# bq25798.net
KiCad netlist of a schematic drawn in Altium Designer
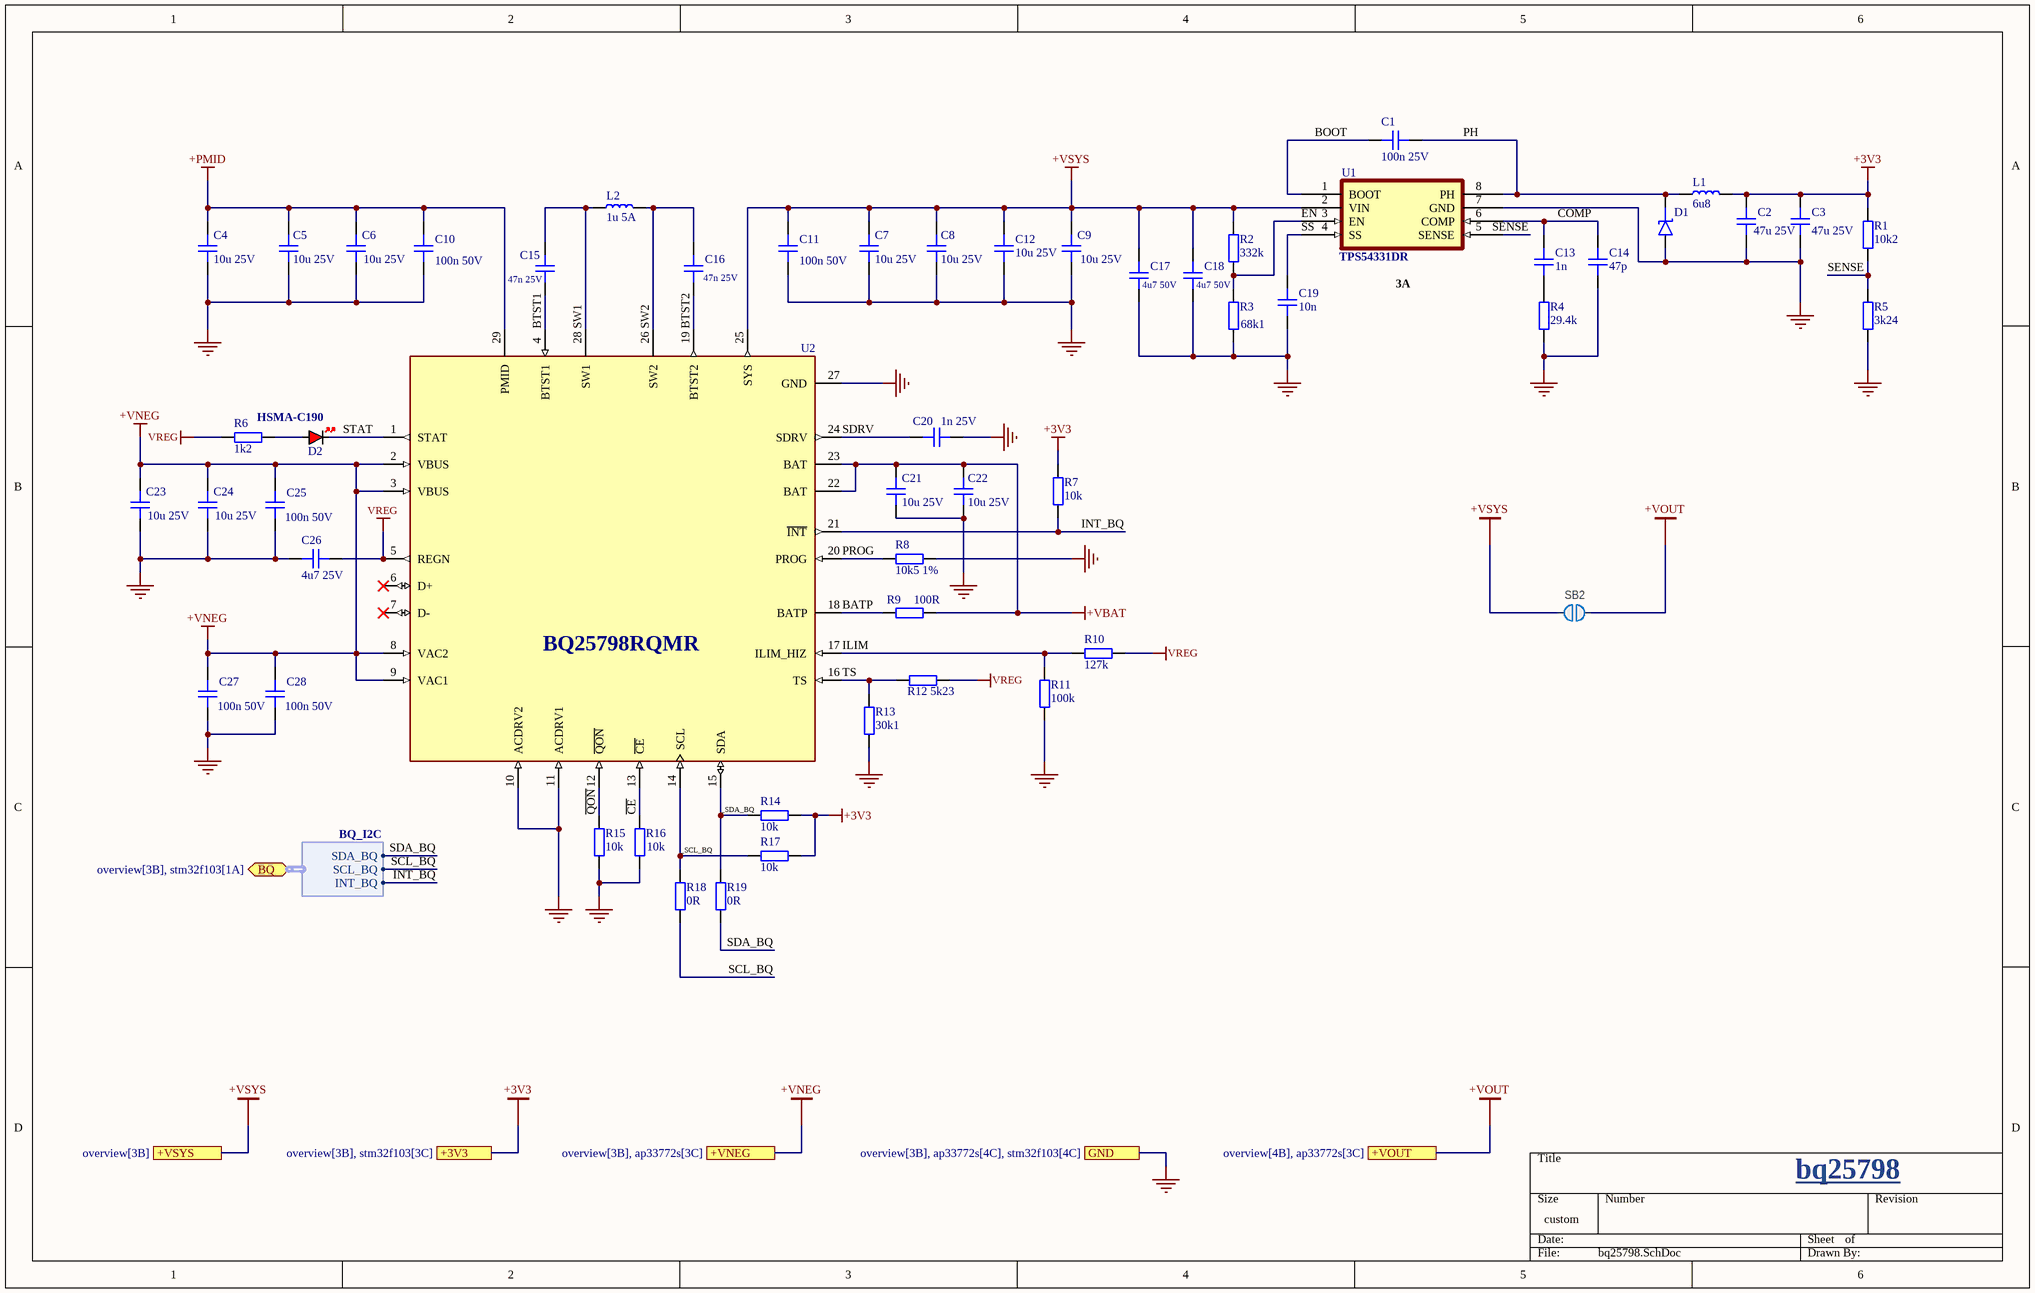
[diagram p0: bq25798.SchDoc]

(export (version "E")
  (design (tool "Eeschema 10.0.6"))
  (components
    (comp (ref "C1")
      (value "100n 25V")
      (footprint "CAP_0805")
      (description "Capacitor SMD 0805")
      (libsource (lib "Schematic-Lib-PhilsLab") (part "CAP_0805"))
    )
    (comp (ref "C2")
      (value "47u 25V")
      (footprint "CAP_1206")
      (description "Capacitor SMD 1206")
      (libsource (lib "Schematic-Lib-PhilsLab") (part "CAP_1206"))
    )
    (comp (ref "C3")
      (value "47u 25V")
      (footprint "CAP_1206")
      (description "Capacitor SMD 1206")
      (libsource (lib "Schematic-Lib-PhilsLab") (part "CAP_1206"))
    )
    (comp (ref "C4")
      (value "10u 25V")
      (footprint "CAP_0603")
      (description "Capacitor SMD 0603")
      (libsource (lib "Sch_Lib") (part "CAP_0603"))
    )
    (comp (ref "C5")
      (value "10u 25V")
      (footprint "CAP_0603")
      (description "Capacitor SMD 0603")
      (libsource (lib "Sch_Lib") (part "CAP_0603"))
    )
    (comp (ref "C6")
      (value "10u 25V")
      (footprint "CAP_0603")
      (description "Capacitor SMD 0603")
      (libsource (lib "Sch_Lib") (part "CAP_0603"))
    )
    (comp (ref "C7")
      (value "10u 25V")
      (footprint "CAP_0603")
      (description "Capacitor SMD 0603")
      (libsource (lib "Sch_Lib") (part "CAP_0603"))
    )
    (comp (ref "C8")
      (value "10u 25V")
      (footprint "CAP_0603")
      (description "Capacitor SMD 0603")
      (libsource (lib "Sch_Lib") (part "CAP_0603"))
    )
    (comp (ref "C9")
      (value "10u 25V")
      (footprint "CAP_0603")
      (description "Capacitor SMD 0603")
      (libsource (lib "Sch_Lib") (part "CAP_0603"))
    )
    (comp (ref "C10")
      (value "100n 50V")
      (footprint "CAP_0402")
      (description "Capacitor SMD 0402")
      (libsource (lib "Sch_Lib") (part "CAP_0402"))
    )
    (comp (ref "C11")
      (value "100n 50V")
      (footprint "CAP_0402")
      (description "Capacitor SMD 0402")
      (libsource (lib "Sch_Lib") (part "CAP_0402"))
    )
    (comp (ref "C12")
      (value "10u 25V")
      (footprint "CAP_0603")
      (description "Capacitor SMD 0603")
      (libsource (lib "Sch_Lib") (part "CAP_0603"))
    )
    (comp (ref "C13")
      (value "1n")
      (footprint "CAP_0603")
      (description "Capacitor SMD 0603")
      (libsource (lib "Schematic-Lib-PhilsLab") (part "CAP_0603"))
    )
    (comp (ref "C14")
      (value "47p")
      (footprint "CAP_0402")
      (description "Capacitor SMD 0402")
      (libsource (lib "Schematic-Lib-PhilsLab") (part "CAP_0402"))
    )
    (comp (ref "C15")
      (value "47n 25V")
      (footprint "CAP_0603")
      (description "Capacitor SMD 0603")
      (libsource (lib "Sch_Lib") (part "CAP_0603"))
    )
    (comp (ref "C16")
      (value "47n 25V")
      (footprint "CAP_0603")
      (description "Capacitor SMD 0603")
      (libsource (lib "Sch_Lib") (part "CAP_0603"))
    )
    (comp (ref "C17")
      (value "4u7 50V")
      (footprint "CAP_1206")
      (description "Capacitor SMD 1206")
      (libsource (lib "Schematic-Lib-PhilsLab") (part "CAP_1206"))
    )
    (comp (ref "C18")
      (value "4u7 50V")
      (footprint "CAP_1206")
      (description "Capacitor SMD 1206")
      (libsource (lib "Schematic-Lib-PhilsLab") (part "CAP_1206"))
    )
    (comp (ref "C19")
      (value "10n")
      (footprint "CAP_0603")
      (description "Capacitor SMD 0603")
      (libsource (lib "Schematic-Lib-PhilsLab") (part "CAP_0603"))
    )
    (comp (ref "C20")
      (value "1n 25V")
      (footprint "CAP_0603")
      (description "Capacitor SMD 0603")
      (libsource (lib "Sch_Lib") (part "CAP_0603"))
    )
    (comp (ref "C21")
      (value "10u 25V")
      (footprint "CAP_0603")
      (description "Capacitor SMD 0603")
      (libsource (lib "Sch_Lib") (part "CAP_0603"))
    )
    (comp (ref "C22")
      (value "10u 25V")
      (footprint "CAP_0603")
      (description "Capacitor SMD 0603")
      (libsource (lib "Sch_Lib") (part "CAP_0603"))
    )
    (comp (ref "C23")
      (value "10u 25V")
      (footprint "CAP_0603")
      (description "Capacitor SMD 0603")
      (libsource (lib "Sch_Lib") (part "CAP_0603"))
    )
    (comp (ref "C24")
      (value "10u 25V")
      (footprint "CAP_0603")
      (description "Capacitor SMD 0603")
      (libsource (lib "Sch_Lib") (part "CAP_0603"))
    )
    (comp (ref "C25")
      (value "100n 50V")
      (footprint "CAP_0402")
      (description "Capacitor SMD 0402")
      (libsource (lib "Sch_Lib") (part "CAP_0402"))
    )
    (comp (ref "C26")
      (value "4u7 25V")
      (footprint "CAP_0402")
      (description "Capacitor SMD 0402")
      (libsource (lib "Sch_Lib") (part "CAP_0402"))
    )
    (comp (ref "C27")
      (value "100n 50V")
      (footprint "CAP_0402")
      (description "Capacitor SMD 0402")
      (libsource (lib "Sch_Lib") (part "CAP_0402"))
    )
    (comp (ref "C28")
      (value "100n 50V")
      (footprint "CAP_0402")
      (description "Capacitor SMD 0402")
      (libsource (lib "Sch_Lib") (part "CAP_0402"))
    )
    (comp (ref "D1")
      (value "Schottky Diode_3")
      (footprint "DIOM5226X100N")
      (description "Schottky Diode SMD SMAF package")
      (libsource (lib "Schematic-Lib-PhilsLab") (part "Schottky Diode_3"))
    )
    (comp (ref "D2")
      (value "HSMA-C190")
      (footprint "LED_HSMA-C190")
      (description "20mA White Lens 90mcd 592nm Amber 170° 1.9V 0603 LED Indication - Discrete ROHS")
      (libsource (lib "Sch_Lib") (part "HSMA-C190"))
    )
    (comp (ref "L1")
      (value "6u8")
      (footprint "ASPI-0630HI-6R8M-T15")
      (description "Inductor SMD 6.8uH 20% 8A Shielded")
      (fields
        (field (name "MANUFACTURER") "ABRACON")
        (field (name "MANUFACTURER PART NUMBER") "ASPI-0630HI-6R8M-T15")
      )
      (libsource (lib "Schematic-Lib-PhilsLab") (part "ASPI-0630HI-6R8M-T15"))
    )
    (comp (ref "L2")
      (value "1u 5A")
      (footprint "IND_AMPLA4020S1R0MT")
      (description "Inductor Power Shielded/Molded Wirewound 1uH 20% 100KHz Carbonyl Powder 5A 0.027Ohm DCR 1616 T/R")
      (fields (field (name "MF") "Abracon") (field (name "MP") "AMPLA4020S1R0MT"))
      (libsource (lib "Sch_Lib") (part "AMPLA4020S1R0MT"))
    )
    (comp (ref "R1")
      (value "10k2")
      (footprint "RES_0603")
      (description "Resistor SMD 0603")
      (libsource (lib "Sch_Lib") (part "RES_0603"))
    )
    (comp (ref "R2")
      (value "332k")
      (footprint "RES_0603")
      (description "Resistor SMD 0603")
      (libsource (lib "Sch_Lib") (part "RES_0603"))
    )
    (comp (ref "R3")
      (value "68k1")
      (footprint "RES_0805")
      (description "Resistor SMD 0805")
      (libsource (lib "Schematic-Lib-PhilsLab") (part "RES_0805"))
    )
    (comp (ref "R4")
      (value "29.4k")
      (footprint "RES_0603")
      (description "Resistor SMD 0603")
      (libsource (lib "Schematic-Lib-PhilsLab") (part "RES_0603"))
    )
    (comp (ref "R5")
      (value "3k24")
      (footprint "RES_0603")
      (description "Resistor SMD 0603")
      (libsource (lib "Sch_Lib") (part "RES_0603"))
    )
    (comp (ref "R6")
      (value "1k2")
      (footprint "RES_0603")
      (description "Resistor SMD 0603")
      (libsource (lib "Sch_Lib") (part "RES_0603"))
    )
    (comp (ref "R7")
      (value "10k")
      (footprint "RES_0603")
      (description "Resistor SMD 0603")
      (libsource (lib "Sch_Lib") (part "RES_0603"))
    )
    (comp (ref "R8")
      (value "10k5 1%")
      (footprint "RES_0603")
      (description "Resistor SMD 0603")
      (libsource (lib "Sch_Lib") (part "RES_0603"))
    )
    (comp (ref "R9")
      (value "100R")
      (footprint "RES_0603")
      (description "Resistor SMD 0603")
      (libsource (lib "Sch_Lib") (part "RES_0603"))
    )
    (comp (ref "R10")
      (value "127k")
      (footprint "RES_0603")
      (description "Resistor SMD 0603")
      (libsource (lib "Sch_Lib") (part "RES_0603"))
    )
    (comp (ref "R11")
      (value "100k")
      (footprint "RES_0603")
      (description "Resistor SMD 0603")
      (libsource (lib "Sch_Lib") (part "RES_0603"))
    )
    (comp (ref "R12")
      (value "5k23")
      (footprint "RES_0603")
      (description "Resistor SMD 0603")
      (libsource (lib "Sch_Lib") (part "RES_0603"))
    )
    (comp (ref "R13")
      (value "30k1")
      (footprint "RES_0603")
      (description "Resistor SMD 0603")
      (libsource (lib "Sch_Lib") (part "RES_0603"))
    )
    (comp (ref "R14")
      (value "10k")
      (footprint "RES_0603")
      (description "Resistor SMD 0603")
      (libsource (lib "Sch_Lib") (part "RES_0603"))
    )
    (comp (ref "R15")
      (value "10k")
      (footprint "RES_0603")
      (description "Resistor SMD 0603")
      (libsource (lib "Sch_Lib") (part "RES_0603"))
    )
    (comp (ref "R16")
      (value "10k")
      (footprint "RES_0603")
      (description "Resistor SMD 0603")
      (libsource (lib "Sch_Lib") (part "RES_0603"))
    )
    (comp (ref "R17")
      (value "10k")
      (footprint "RES_0603")
      (description "Resistor SMD 0603")
      (libsource (lib "Sch_Lib") (part "RES_0603"))
    )
    (comp (ref "R18")
      (value "0R")
      (footprint "RES_0603")
      (description "Resistor SMD 0603")
      (libsource (lib "Sch_Lib") (part "RES_0603"))
    )
    (comp (ref "R19")
      (value "0R")
      (footprint "RES_0603")
      (description "Resistor SMD 0603")
      (libsource (lib "Sch_Lib") (part "RES_0603"))
    )
    (comp (ref "SB2")
      (value "Solderbridge")
      (footprint "Solderbridge")
      (fields (field (name "MANUFACTURER") "N.A.") (field (name "AUTHOR") "rsk"))
      (libsource (lib "Sch_Lib") (part "Solderbridge"))
    )
    (comp (ref "U1")
      (value "TPS54331DR")
      (footprint "SOIC127P599X175-8N")
      (libsource (lib "Sch_Lib") (part "TPS54331DR"))
    )
    (comp (ref "U2")
      (value "BQ25798RQMR")
      (footprint "IC_BQ25798RQMR")
      (description "IÂ²C controlled, 1-4-cell, 5-A buck-boost solar battery charger with dual-input selector and MPPT")
      (fields (field (name "MF") "Texas Instruments"))
      (libsource (lib "Sch_Lib") (part "BQ25798RQMR"))
    )
  )
  (nets
    (net (code "2") (name "+3V3") (class "Default")
      (node (ref "C2") (pin "2") (pinfunction "2_2") (pintype "passive"))
      (node (ref "C3") (pin "2") (pinfunction "2_2") (pintype "passive"))
      (node (ref "L1") (pin "2") (pinfunction "2_2") (pintype "passive"))
      (node (ref "R1") (pin "2") (pinfunction "2_2") (pintype "passive"))
      (node (ref "R14") (pin "2") (pinfunction "2_2") (pintype "passive"))
      (node (ref "R17") (pin "1") (pinfunction "1_1") (pintype "passive"))
      (node (ref "R7") (pin "2") (pinfunction "2_2") (pintype "passive"))
    )
    (net (code "3") (name "+PMID") (class "Default")
      (node (ref "C10") (pin "2") (pinfunction "2_2") (pintype "passive"))
      (node (ref "C4") (pin "2") (pinfunction "2_2") (pintype "passive"))
      (node (ref "C5") (pin "2") (pinfunction "2_2") (pintype "passive"))
      (node (ref "C6") (pin "2") (pinfunction "2_2") (pintype "passive"))
      (node (ref "U2") (pin "29") (pinfunction "PMID_29") (pintype "passive"))
    )
    (net (code "4") (name "+VBAT") (class "Default")
      (node (ref "C21") (pin "2") (pinfunction "2_2") (pintype "passive"))
      (node (ref "C22") (pin "2") (pinfunction "2_2") (pintype "passive"))
      (node (ref "R9") (pin "2") (pinfunction "2_2") (pintype "passive"))
      (node (ref "U2") (pin "22") (pinfunction "BAT_22") (pintype "power_in"))
      (node (ref "U2") (pin "23") (pinfunction "BAT_23") (pintype "power_in"))
    )
    (net (code "5") (name "+VNEG") (class "Default")
      (node (ref "C23") (pin "2") (pinfunction "2_2") (pintype "passive"))
      (node (ref "C24") (pin "2") (pinfunction "2_2") (pintype "passive"))
      (node (ref "C25") (pin "2") (pinfunction "2_2") (pintype "passive"))
      (node (ref "C27") (pin "2") (pinfunction "2_2") (pintype "passive"))
      (node (ref "C28") (pin "2") (pinfunction "2_2") (pintype "passive"))
      (node (ref "U2") (pin "2") (pinfunction "VBUS_2") (pintype "input"))
      (node (ref "U2") (pin "3") (pinfunction "VBUS_3") (pintype "input"))
      (node (ref "U2") (pin "8") (pinfunction "VAC2_8") (pintype "input"))
      (node (ref "U2") (pin "9") (pinfunction "VAC1_9") (pintype "input"))
    )
    (net (code "6") (name "+VOUT") (class "Default")
      (node (ref "SB2") (pin "1") (pinfunction "0_1") (pintype "passive"))
    )
    (net (code "7") (name "+VSYS") (class "Default")
      (node (ref "C11") (pin "2") (pinfunction "2_2") (pintype "passive"))
      (node (ref "C12") (pin "2") (pinfunction "2_2") (pintype "passive"))
      (node (ref "C17") (pin "2") (pinfunction "2_2") (pintype "passive"))
      (node (ref "C18") (pin "2") (pinfunction "2_2") (pintype "passive"))
      (node (ref "C7") (pin "2") (pinfunction "2_2") (pintype "passive"))
      (node (ref "C8") (pin "2") (pinfunction "2_2") (pintype "passive"))
      (node (ref "C9") (pin "2") (pinfunction "2_2") (pintype "passive"))
      (node (ref "R2") (pin "2") (pinfunction "2_2") (pintype "passive"))
      (node (ref "SB2") (pin "2") (pinfunction "1_2") (pintype "passive"))
      (node (ref "U1") (pin "2") (pinfunction "VIN_2") (pintype "power_in"))
      (node (ref "U2") (pin "25") (pinfunction "SYS_25") (pintype "output"))
    )
    (net (code "8") (name "/BATP") (class "Default")
      (node (ref "R9") (pin "1") (pinfunction "1_1") (pintype "passive"))
      (node (ref "U2") (pin "18") (pinfunction "BATP_18") (pintype "power_in"))
    )
    (net (code "9") (name "/BOOT") (class "Default")
      (node (ref "C1") (pin "1") (pinfunction "1_1") (pintype "passive"))
      (node (ref "U1") (pin "1") (pinfunction "BOOT_1") (pintype "power_in"))
    )
    (net (code "10") (name "/BTST1") (class "Default")
      (node (ref "C15") (pin "1") (pinfunction "1_1") (pintype "passive"))
      (node (ref "U2") (pin "4") (pinfunction "BTST1_4") (pintype "input"))
    )
    (net (code "11") (name "/BTST2") (class "Default")
      (node (ref "C16") (pin "1") (pinfunction "1_1") (pintype "passive"))
      (node (ref "U2") (pin "19") (pinfunction "BTST2_19") (pintype "output"))
    )
    (net (code "12") (name "/COMP") (class "Default")
      (node (ref "C13") (pin "2") (pinfunction "2_2") (pintype "passive"))
      (node (ref "C14") (pin "2") (pinfunction "2_2") (pintype "passive"))
      (node (ref "U1") (pin "6") (pinfunction "COMP_6") (pintype "input"))
    )
    (net (code "13") (name "/EN") (class "Default")
      (node (ref "R2") (pin "1") (pinfunction "1_1") (pintype "passive"))
      (node (ref "R3") (pin "2") (pinfunction "2_2") (pintype "passive"))
      (node (ref "U1") (pin "3") (pinfunction "EN_3") (pintype "input"))
    )
    (net (code "14") (name "/ILIM") (class "Default")
      (node (ref "R10") (pin "1") (pinfunction "1_1") (pintype "passive"))
      (node (ref "R11") (pin "2") (pinfunction "2_2") (pintype "passive"))
      (node (ref "U2") (pin "17") (pinfunction "ILIM_HIZ_17") (pintype "input"))
    )
    (net (code "15") (name "/INT_BQ") (class "Default")
      (node (ref "R7") (pin "1") (pinfunction "1_1") (pintype "passive"))
      (node (ref "U2") (pin "21") (pinfunction "~{INT}_21") (pintype "output"))
    )
    (net (code "16") (name "/PH") (class "Default")
      (node (ref "C1") (pin "2") (pinfunction "2_2") (pintype "passive"))
      (node (ref "D1") (pin "K") (pinfunction "K_K") (pintype "passive"))
      (node (ref "L1") (pin "1") (pinfunction "1_1") (pintype "passive"))
      (node (ref "U1") (pin "8") (pinfunction "PH_8") (pintype "power_in"))
    )
    (net (code "17") (name "/PROG") (class "Default")
      (node (ref "R8") (pin "2") (pinfunction "2_2") (pintype "passive"))
      (node (ref "U2") (pin "20") (pinfunction "PROG_20") (pintype "input"))
    )
    (net (code "18") (name "/SCL_BQ") (class "Default")
      (node (ref "R18") (pin "2") (pinfunction "2_2") (pintype "passive"))
    )
    (net (code "19") (name "/SDA_BQ") (class "Default")
      (node (ref "R19") (pin "1") (pinfunction "1_1") (pintype "passive"))
    )
    (net (code "20") (name "/SDRV") (class "Default")
      (node (ref "C20") (pin "1") (pinfunction "1_1") (pintype "passive"))
      (node (ref "U2") (pin "24") (pinfunction "SDRV_24") (pintype "output"))
    )
    (net (code "21") (name "/SENSE") (class "Default")
      (node (ref "R1") (pin "1") (pinfunction "1_1") (pintype "passive"))
      (node (ref "R5") (pin "2") (pinfunction "2_2") (pintype "passive"))
      (node (ref "U1") (pin "5") (pinfunction "SENSE_5") (pintype "input"))
    )
    (net (code "22") (name "/SS") (class "Default")
      (node (ref "C19") (pin "2") (pinfunction "2_2") (pintype "passive"))
      (node (ref "U1") (pin "4") (pinfunction "SS_4") (pintype "input"))
    )
    (net (code "23") (name "/STAT") (class "Default")
      (node (ref "D2") (pin "K") (pinfunction "K_K") (pintype "passive"))
      (node (ref "U2") (pin "1") (pinfunction "STAT_1") (pintype "output"))
    )
    (net (code "24") (name "/SW1") (class "Default")
      (node (ref "C15") (pin "2") (pinfunction "2_2") (pintype "passive"))
      (node (ref "L2") (pin "1") (pinfunction "1_1") (pintype "passive"))
      (node (ref "U2") (pin "28") (pinfunction "SW1_28") (pintype "passive"))
    )
    (net (code "25") (name "/SW2") (class "Default")
      (node (ref "C16") (pin "2") (pinfunction "2_2") (pintype "passive"))
      (node (ref "L2") (pin "2") (pinfunction "2_2") (pintype "passive"))
      (node (ref "U2") (pin "26") (pinfunction "SW2_26") (pintype "passive"))
    )
    (net (code "26") (name "/TS") (class "Default")
      (node (ref "R12") (pin "1") (pinfunction "1_1") (pintype "passive"))
      (node (ref "R13") (pin "2") (pinfunction "2_2") (pintype "passive"))
      (node (ref "U2") (pin "16") (pinfunction "TS_16") (pintype "input"))
    )
    (net (code "27") (name "/_SCL_BQ") (class "Default")
      (node (ref "R17") (pin "2") (pinfunction "2_2") (pintype "passive"))
      (node (ref "R18") (pin "1") (pinfunction "1_1") (pintype "passive"))
      (node (ref "U2") (pin "14") (pinfunction "SCL_14") (pintype "input"))
    )
    (net (code "28") (name "/_SDA_BQ") (class "Default")
      (node (ref "R14") (pin "1") (pinfunction "1_1") (pintype "passive"))
      (node (ref "R19") (pin "2") (pinfunction "2_2") (pintype "passive"))
      (node (ref "U2") (pin "15") (pinfunction "SDA_15") (pintype "bidirectional"))
    )
    (net (code "30") (name "/~{CE}") (class "Default")
      (node (ref "R16") (pin "2") (pinfunction "2_2") (pintype "passive"))
      (node (ref "U2") (pin "13") (pinfunction "~{CE}_13") (pintype "input"))
    )
    (net (code "31") (name "/~{QON}") (class "Default")
      (node (ref "R15") (pin "2") (pinfunction "2_2") (pintype "passive"))
      (node (ref "U2") (pin "12") (pinfunction "~{QON}_12") (pintype "input"))
    )
    (net (code "32") (name "GND") (class "Default")
      (node (ref "C10") (pin "1") (pinfunction "1_1") (pintype "passive"))
      (node (ref "C11") (pin "1") (pinfunction "1_1") (pintype "passive"))
      (node (ref "C12") (pin "1") (pinfunction "1_1") (pintype "passive"))
      (node (ref "C14") (pin "1") (pinfunction "1_1") (pintype "passive"))
      (node (ref "C17") (pin "1") (pinfunction "1_1") (pintype "passive"))
      (node (ref "C18") (pin "1") (pinfunction "1_1") (pintype "passive"))
      (node (ref "C19") (pin "1") (pinfunction "1_1") (pintype "passive"))
      (node (ref "C2") (pin "1") (pinfunction "1_1") (pintype "passive"))
      (node (ref "C20") (pin "2") (pinfunction "2_2") (pintype "passive"))
      (node (ref "C21") (pin "1") (pinfunction "1_1") (pintype "passive"))
      (node (ref "C22") (pin "1") (pinfunction "1_1") (pintype "passive"))
      (node (ref "C23") (pin "1") (pinfunction "1_1") (pintype "passive"))
      (node (ref "C24") (pin "1") (pinfunction "1_1") (pintype "passive"))
      (node (ref "C25") (pin "1") (pinfunction "1_1") (pintype "passive"))
      (node (ref "C26") (pin "2") (pinfunction "2_2") (pintype "passive"))
      (node (ref "C27") (pin "1") (pinfunction "1_1") (pintype "passive"))
      (node (ref "C28") (pin "1") (pinfunction "1_1") (pintype "passive"))
      (node (ref "C3") (pin "1") (pinfunction "1_1") (pintype "passive"))
      (node (ref "C4") (pin "1") (pinfunction "1_1") (pintype "passive"))
      (node (ref "C5") (pin "1") (pinfunction "1_1") (pintype "passive"))
      (node (ref "C6") (pin "1") (pinfunction "1_1") (pintype "passive"))
      (node (ref "C7") (pin "1") (pinfunction "1_1") (pintype "passive"))
      (node (ref "C8") (pin "1") (pinfunction "1_1") (pintype "passive"))
      (node (ref "C9") (pin "1") (pinfunction "1_1") (pintype "passive"))
      (node (ref "D1") (pin "A") (pinfunction "A_A") (pintype "passive"))
      (node (ref "R11") (pin "1") (pinfunction "1_1") (pintype "passive"))
      (node (ref "R13") (pin "1") (pinfunction "1_1") (pintype "passive"))
      (node (ref "R15") (pin "1") (pinfunction "1_1") (pintype "passive"))
      (node (ref "R16") (pin "1") (pinfunction "1_1") (pintype "passive"))
      (node (ref "R3") (pin "1") (pinfunction "1_1") (pintype "passive"))
      (node (ref "R4") (pin "1") (pinfunction "1_1") (pintype "passive"))
      (node (ref "R5") (pin "1") (pinfunction "1_1") (pintype "passive"))
      (node (ref "R8") (pin "1") (pinfunction "1_1") (pintype "passive"))
      (node (ref "U1") (pin "7") (pinfunction "GND_7") (pintype "power_in"))
      (node (ref "U2") (pin "10") (pinfunction "ACDRV2_10") (pintype "input"))
      (node (ref "U2") (pin "11") (pinfunction "ACDRV1_11") (pintype "input"))
      (node (ref "U2") (pin "27") (pinfunction "GND_27") (pintype "power_in"))
    )
    (net (code "33") (name "Net-(C13-Pad1)") (class "Default")
      (node (ref "C13") (pin "1") (pinfunction "1_1") (pintype "passive"))
      (node (ref "R4") (pin "2") (pinfunction "2_2") (pintype "passive"))
    )
    (net (code "34") (name "Net-(D2-PadA)") (class "Default")
      (node (ref "D2") (pin "A") (pinfunction "A_A") (pintype "passive"))
      (node (ref "R6") (pin "2") (pinfunction "2_2") (pintype "passive"))
    )
    (net (code "35") (name "VREG") (class "Default")
      (node (ref "C26") (pin "1") (pinfunction "1_1") (pintype "passive"))
      (node (ref "R10") (pin "2") (pinfunction "2_2") (pintype "passive"))
      (node (ref "R12") (pin "2") (pinfunction "2_2") (pintype "passive"))
      (node (ref "R6") (pin "1") (pinfunction "1_1") (pintype "passive"))
      (node (ref "U2") (pin "5") (pinfunction "REGN_5") (pintype "output"))
    )
    (net (code "36") (name "unconnected-(U2-D+-Pad6)") (class "Default")
      (node (ref "U2") (pin "6") (pinfunction "D+_6") (pintype "bidirectional+no_connect"))
    )
    (net (code "37") (name "unconnected-(U2-D--Pad7)") (class "Default")
      (node (ref "U2") (pin "7") (pinfunction "D-_7") (pintype "bidirectional+no_connect"))
    )
  )
)
